# RS-485.net
KiCad netlist of a schematic drawn in Altium Designer
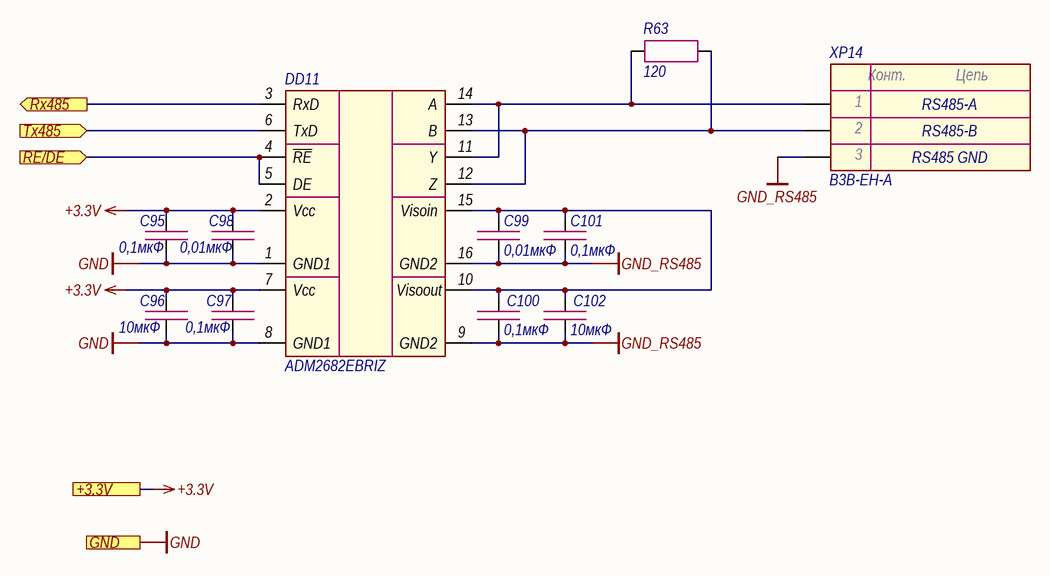
[diagram p0: RS-485.SchDoc]

(export (version "E")
  (design (tool "Eeschema 10.0.6"))
  (components
    (comp (ref "C95")
      (value "0,1мкФ")
      (footprint "Pcb_library:CAP_0603")
      (fields (field (name "MANUFACTURER") "Murata"))
      (libsource (lib "Schem_library") (part "Capacitor"))
    )
    (comp (ref "C96")
      (value "10мкФ")
      (footprint "Pcb_library:CAP_0603")
      (fields (field (name "MANUFACTURER") "Murata"))
      (libsource (lib "Schem_library") (part "Capacitor"))
    )
    (comp (ref "C97")
      (value "0,1мкФ")
      (footprint "Pcb_library:CAP_0603")
      (fields (field (name "MANUFACTURER") "Murata"))
      (libsource (lib "Schem_library") (part "Capacitor"))
    )
    (comp (ref "C98")
      (value "0,01мкФ")
      (footprint "Pcb_library:CAP_0603")
      (fields (field (name "MANUFACTURER") "Murata"))
      (libsource (lib "Schem_library") (part "Capacitor"))
    )
    (comp (ref "C99")
      (value "0,01мкФ")
      (footprint "Pcb_library:CAP_0603")
      (fields (field (name "MANUFACTURER") "Murata"))
      (libsource (lib "Schem_library") (part "Capacitor"))
    )
    (comp (ref "C100")
      (value "0,1мкФ")
      (footprint "Pcb_library:CAP_0603")
      (fields (field (name "MANUFACTURER") "Murata"))
      (libsource (lib "Schem_library") (part "Capacitor"))
    )
    (comp (ref "C101")
      (value "0,1мкФ")
      (footprint "Pcb_library:CAP_0603")
      (fields (field (name "MANUFACTURER") "Murata"))
      (libsource (lib "Schem_library") (part "Capacitor"))
    )
    (comp (ref "C102")
      (value "10мкФ")
      (footprint "Pcb_library:CAP_0603")
      (fields (field (name "MANUFACTURER") "Murata"))
      (libsource (lib "Schem_library") (part "Capacitor"))
    )
    (comp (ref "DD11")
      (value "ADM2682EBRIZ")
      (footprint "Pcb_library:SOIC-16IC")
      (fields (field (name "MANUFACTURER") "Analog Devices"))
      (libsource (lib "Schem_library") (part "ADM2682EBRIZ"))
    )
    (comp (ref "R63")
      (value "120")
      (footprint "Pcb_library:RES_0603")
      (fields (field (name "MANUFACTURER") "Yageo"))
      (libsource (lib "Schem_library") (part "Resistor"))
    )
    (comp (ref "XP14")
      (value "B3B-EH-A")
      (footprint "B3B-EH-A")
      (fields (field (name "MANUFACTURER") "JST"))
      (libsource (lib "Schem_library") (part "Connector-3"))
    )
  )
  (nets
    (net (code "1") (name "+3.3V") (class "Default")
      (node (ref "C95") (pin "1") (pinfunction "1_1") (pintype "passive"))
      (node (ref "C96") (pin "1") (pinfunction "1_1") (pintype "passive"))
      (node (ref "C97") (pin "1") (pinfunction "1_1") (pintype "passive"))
      (node (ref "C98") (pin "2") (pinfunction "2_2") (pintype "passive"))
      (node (ref "DD11") (pin "2") (pinfunction "Vcc_2") (pintype "passive"))
      (node (ref "DD11") (pin "7") (pinfunction "Vcc_7") (pintype "passive"))
    )
    (net (code "2") (name "/RE{slash}DE") (class "Default")
      (node (ref "DD11") (pin "4") (pinfunction "~{RE}_4") (pintype "passive"))
      (node (ref "DD11") (pin "5") (pinfunction "DE_5") (pintype "passive"))
    )
    (net (code "3") (name "/Rx485") (class "Default")
      (node (ref "DD11") (pin "3") (pinfunction "RxD_3") (pintype "passive"))
    )
    (net (code "4") (name "/Tx485") (class "Default")
      (node (ref "DD11") (pin "6") (pinfunction "TxD_6") (pintype "passive"))
    )
    (net (code "5") (name "GND") (class "Default")
      (node (ref "C95") (pin "2") (pinfunction "2_2") (pintype "passive"))
      (node (ref "C96") (pin "2") (pinfunction "2_2") (pintype "passive"))
      (node (ref "C97") (pin "2") (pinfunction "2_2") (pintype "passive"))
      (node (ref "C98") (pin "1") (pinfunction "1_1") (pintype "passive"))
      (node (ref "DD11") (pin "1") (pinfunction "GND1_1") (pintype "passive"))
      (node (ref "DD11") (pin "8") (pinfunction "GND1_8") (pintype "passive"))
    )
    (net (code "6") (name "GND_RS485") (class "Default")
      (node (ref "C100") (pin "2") (pinfunction "2_2") (pintype "passive"))
      (node (ref "C101") (pin "2") (pinfunction "2_2") (pintype "passive"))
      (node (ref "C102") (pin "2") (pinfunction "2_2") (pintype "passive"))
      (node (ref "C99") (pin "1") (pinfunction "1_1") (pintype "passive"))
      (node (ref "DD11") (pin "16") (pinfunction "GND2_16") (pintype "passive"))
      (node (ref "DD11") (pin "9") (pinfunction "GND2_9") (pintype "passive"))
      (node (ref "XP14") (pin "3") (pintype "passive"))
    )
    (net (code "7") (name "Net-(DD11-A)") (class "Default")
      (node (ref "DD11") (pin "11") (pinfunction "Y_11") (pintype "passive"))
      (node (ref "DD11") (pin "14") (pinfunction "A_14") (pintype "passive"))
      (node (ref "R63") (pin "1") (pinfunction "1_1") (pintype "passive"))
      (node (ref "XP14") (pin "1") (pintype "passive"))
    )
    (net (code "8") (name "Net-(DD11-B)") (class "Default")
      (node (ref "DD11") (pin "12") (pinfunction "Z_12") (pintype "passive"))
      (node (ref "DD11") (pin "13") (pinfunction "B_13") (pintype "passive"))
      (node (ref "R63") (pin "2") (pinfunction "2_2") (pintype "passive"))
      (node (ref "XP14") (pin "2") (pintype "passive"))
    )
    (net (code "9") (name "Net-(DD11-Visoin)") (class "Default")
      (node (ref "C100") (pin "1") (pinfunction "1_1") (pintype "passive"))
      (node (ref "C101") (pin "1") (pinfunction "1_1") (pintype "passive"))
      (node (ref "C102") (pin "1") (pinfunction "1_1") (pintype "passive"))
      (node (ref "C99") (pin "2") (pinfunction "2_2") (pintype "passive"))
      (node (ref "DD11") (pin "10") (pinfunction "Visoout_10") (pintype "passive"))
      (node (ref "DD11") (pin "15") (pinfunction "Visoin_15") (pintype "passive"))
    )
  )
)
